# 9_-Power.net
KiCad netlist of a schematic drawn in Altium Designer
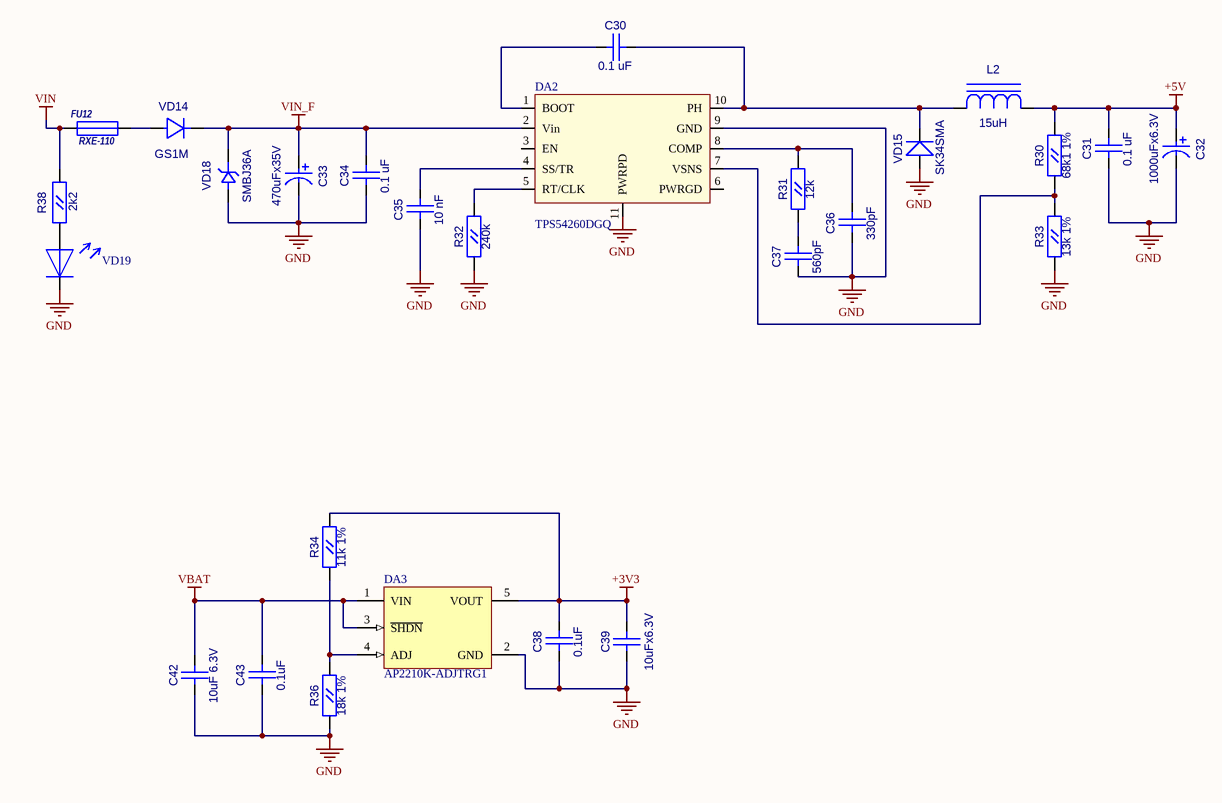
[diagram p0: [9]-Power.SchDoc]

(export (version "E")
  (design (tool "Eeschema 10.0.6"))
  (components
    (comp (ref "C30")
      (value "0.1 uF")
      (footprint "CC0603")
      (description "CC0603")
      (libsource (lib "gprs_modem_2") (part "CC0603"))
    )
    (comp (ref "C31")
      (value "0.1 uF")
      (footprint "CC0603")
      (description "CC0603")
      (libsource (lib "gprs_modem_2") (part "CC0603"))
    )
    (comp (ref "C32")
      (value "1000uFx6.3V")
      (footprint "CC8X3.5")
      (description "CAP0.35")
      (libsource (lib "gprs_modem_2") (part "CAP0.35"))
    )
    (comp (ref "C33")
      (value "470uFx35V")
      (footprint "CC16X10_CAP0.5(1)(Primary)")
      (description "CAP0.5(1)")
      (libsource (lib "gprs_modem_2") (part "CAP0.5(1)"))
    )
    (comp (ref "C34")
      (value "0.1 uF")
      (footprint "CC0603")
      (description "CC0603")
      (libsource (lib "gprs_modem_2") (part "CC0603"))
    )
    (comp (ref "C35")
      (value "10 nF")
      (footprint "CC0603")
      (description "CC0603")
      (libsource (lib "gprs_modem_2") (part "CC0603"))
    )
    (comp (ref "C36")
      (value "330pF")
      (footprint "CC0603")
      (description "CC0603")
      (libsource (lib "gprs_modem_2") (part "CC0603"))
    )
    (comp (ref "C37")
      (value "560pF")
      (footprint "CC0603")
      (description "CC0603")
      (libsource (lib "gprs_modem_2") (part "CC0603"))
    )
    (comp (ref "C38")
      (value "0.1uF")
      (footprint "CC0603")
      (description "CC0603")
      (libsource (lib "gprs_modem_2") (part "CC0603"))
    )
    (comp (ref "C39")
      (value "10uFx6.3V")
      (footprint "CC0805")
      (description "CC0805")
      (libsource (lib "gprs_modem_2") (part "CC0805"))
    )
    (comp (ref "C42")
      (value "10uF 6.3V")
      (footprint "CC0805")
      (description "CC0805")
      (libsource (lib "gprs_modem_2") (part "CC0805"))
    )
    (comp (ref "C43")
      (value "0.1uF")
      (footprint "CC0603")
      (description "CC0603")
      (libsource (lib "gprs_modem_2") (part "CC0603"))
    )
    (comp (ref "DA2")
      (value "TPS54260DGQ")
      (footprint "S-PDSO-G10")
      (libsource (lib "gprs_modem_2") (part "TPS54260DGQ"))
    )
    (comp (ref "DA3")
      (value "AP2210K-ADJTRG1")
      (footprint "SOT23-5")
      (fields (field (name "PUBLISHER") "Altium Limited"))
      (libsource (lib "gprs_modem_2") (part "MCP1824T-ADJE/OT"))
    )
    (comp (ref "FU12")
      (value "RXE-110")
      (footprint "RXE-110")
      (libsource (lib "gprs_modem_2") (part "RXE-110"))
    )
    (comp (ref "L2")
      (value "15uH")
      (footprint "SDR0805")
      (description "SDR0805")
      (libsource (lib "gprs_modem_2") (part "SDR0805"))
    )
    (comp (ref "R30")
      (value "68k1 1%")
      (footprint "RC0603")
      (description "RC0603")
      (libsource (lib "gprs_modem_2") (part "RC0603"))
    )
    (comp (ref "R31")
      (value "12k")
      (footprint "RC0603")
      (description "RC0603")
      (libsource (lib "gprs_modem_2") (part "RC0603"))
    )
    (comp (ref "R32")
      (value "240k")
      (footprint "RC0603")
      (description "RC0603")
      (libsource (lib "gprs_modem_2") (part "RC0603"))
    )
    (comp (ref "R33")
      (value "13k 1%")
      (footprint "RC0603")
      (description "RC0603")
      (libsource (lib "gprs_modem_2") (part "RC0603"))
    )
    (comp (ref "R34")
      (value "11k 1%")
      (footprint "RC0603")
      (description "RC0603")
      (libsource (lib "gprs_modem_2") (part "RC0603"))
    )
    (comp (ref "R36")
      (value "18k 1%")
      (footprint "RC0603")
      (description "RC0603")
      (libsource (lib "gprs_modem_2") (part "RC0603"))
    )
    (comp (ref "R38")
      (value "2k2")
      (footprint "RC0603")
      (description "RC0603")
      (libsource (lib "gprs_modem_2") (part "RC0603"))
    )
    (comp (ref "VD14") (value "GS1M") (footprint "SMA") (libsource (lib "gprs_modem_2") (part "GS1M")))
    (comp (ref "VD15")
      (value "SK34SMA")
      (footprint "SMA")
      (description "Schottky Rectifier")
      (libsource (lib "gprs_modem") (part "SK34SMA"))
    )
    (comp (ref "VD18") (value "SMBJ36A") (footprint "SMB") (libsource (lib "gprs_modem_2") (part "SMBJ")))
    (comp (ref "VD19")
      (value "LED_0805")
      (footprint "LED0805")
      (libsource (lib "gprs_modem_2") (part "LED_0805"))
    )
  )
  (nets
    (net (code "1") (name "+3V3") (class "Default")
      (node (ref "C38") (pin "1") (pinfunction "A_1") (pintype "passive"))
      (node (ref "C39") (pin "2") (pinfunction "B_2") (pintype "passive"))
      (node (ref "DA3") (pin "5") (pinfunction "VOUT_5") (pintype "power_in"))
      (node (ref "R34") (pin "2") (pinfunction "B_2") (pintype "passive"))
    )
    (net (code "2") (name "+5V") (class "Default")
      (node (ref "C31") (pin "1") (pinfunction "A_1") (pintype "passive"))
      (node (ref "C32") (pin "1") (pintype "passive"))
      (node (ref "L2") (pin "2") (pinfunction "A_2") (pintype "passive"))
      (node (ref "R30") (pin "2") (pinfunction "B_2") (pintype "passive"))
    )
    (net (code "3") (name "GND") (class "Default")
      (node (ref "C31") (pin "2") (pinfunction "B_2") (pintype "passive"))
      (node (ref "C32") (pin "2") (pintype "passive"))
      (node (ref "C33") (pin "1") (pintype "passive"))
      (node (ref "C34") (pin "2") (pinfunction "B_2") (pintype "passive"))
      (node (ref "C35") (pin "2") (pinfunction "B_2") (pintype "passive"))
      (node (ref "C36") (pin "2") (pinfunction "B_2") (pintype "passive"))
      (node (ref "C37") (pin "2") (pinfunction "B_2") (pintype "passive"))
      (node (ref "C38") (pin "2") (pinfunction "B_2") (pintype "passive"))
      (node (ref "C39") (pin "1") (pinfunction "A_1") (pintype "passive"))
      (node (ref "C42") (pin "1") (pinfunction "A_1") (pintype "passive"))
      (node (ref "C43") (pin "2") (pinfunction "B_2") (pintype "passive"))
      (node (ref "DA2") (pin "11") (pinfunction "PWRPD_11") (pintype "passive"))
      (node (ref "DA2") (pin "9") (pinfunction "GND_9") (pintype "passive"))
      (node (ref "DA3") (pin "2") (pinfunction "GND_2") (pintype "power_in"))
      (node (ref "R32") (pin "1") (pinfunction "A_1") (pintype "passive"))
      (node (ref "R33") (pin "1") (pinfunction "A_1") (pintype "passive"))
      (node (ref "R36") (pin "1") (pinfunction "A_1") (pintype "passive"))
      (node (ref "VD15") (pin "1") (pinfunction "A_1") (pintype "passive"))
      (node (ref "VD18") (pin "1") (pinfunction "A_1") (pintype "passive"))
      (node (ref "VD19") (pin "2") (pintype "passive"))
    )
    (net (code "4") (name "Net-(C30-A)") (class "Default")
      (node (ref "C30") (pin "1") (pinfunction "A_1") (pintype "passive"))
      (node (ref "DA2") (pin "10") (pinfunction "PH_10") (pintype "passive"))
      (node (ref "L2") (pin "1") (pinfunction "C_1") (pintype "passive"))
      (node (ref "VD15") (pin "2") (pinfunction "K_2") (pintype "passive"))
    )
    (net (code "5") (name "Net-(C30-B)") (class "Default")
      (node (ref "C30") (pin "2") (pinfunction "B_2") (pintype "passive"))
      (node (ref "DA2") (pin "1") (pinfunction "BOOT_1") (pintype "passive"))
    )
    (net (code "6") (name "Net-(C35-A)") (class "Default")
      (node (ref "C35") (pin "1") (pinfunction "A_1") (pintype "passive"))
      (node (ref "DA2") (pin "4") (pinfunction "SS/TR_4") (pintype "passive"))
    )
    (net (code "7") (name "Net-(C36-A)") (class "Default")
      (node (ref "C36") (pin "1") (pinfunction "A_1") (pintype "passive"))
      (node (ref "DA2") (pin "8") (pinfunction "COMP_8") (pintype "passive"))
      (node (ref "R31") (pin "2") (pinfunction "B_2") (pintype "passive"))
    )
    (net (code "8") (name "Net-(C37-A)") (class "Default")
      (node (ref "C37") (pin "1") (pinfunction "A_1") (pintype "passive"))
      (node (ref "R31") (pin "1") (pinfunction "A_1") (pintype "passive"))
    )
    (net (code "9") (name "Net-(DA2-RT{slash}CLK)") (class "Default")
      (node (ref "DA2") (pin "5") (pinfunction "RT/CLK_5") (pintype "passive"))
      (node (ref "R32") (pin "2") (pinfunction "B_2") (pintype "passive"))
    )
    (net (code "10") (name "Net-(DA2-VSNS)") (class "Default")
      (node (ref "DA2") (pin "7") (pinfunction "VSNS_7") (pintype "passive"))
      (node (ref "R30") (pin "1") (pinfunction "A_1") (pintype "passive"))
      (node (ref "R33") (pin "2") (pinfunction "B_2") (pintype "passive"))
    )
    (net (code "11") (name "Net-(DA3-ADJ)") (class "Default")
      (node (ref "DA3") (pin "4") (pinfunction "ADJ_4") (pintype "input"))
      (node (ref "R34") (pin "1") (pinfunction "A_1") (pintype "passive"))
      (node (ref "R36") (pin "2") (pinfunction "B_2") (pintype "passive"))
    )
    (net (code "12") (name "Net-(R38-A)") (class "Default")
      (node (ref "R38") (pin "1") (pinfunction "A_1") (pintype "passive"))
      (node (ref "VD19") (pin "1") (pintype "passive"))
    )
    (net (code "13") (name "Net-(VD14-A)") (class "Default")
      (node (ref "FU12") (pin "2") (pintype "passive"))
      (node (ref "VD14") (pin "1") (pinfunction "A_1") (pintype "passive"))
    )
    (net (code "14") (name "VBAT") (class "Default")
      (node (ref "C42") (pin "2") (pinfunction "B_2") (pintype "passive"))
      (node (ref "C43") (pin "1") (pinfunction "A_1") (pintype "passive"))
      (node (ref "DA3") (pin "1") (pinfunction "VIN_1") (pintype "power_in"))
      (node (ref "DA3") (pin "3") (pinfunction "~{SHDN}_3") (pintype "input"))
    )
    (net (code "15") (name "VIN") (class "Default")
      (node (ref "FU12") (pin "1") (pintype "passive"))
      (node (ref "R38") (pin "2") (pinfunction "B_2") (pintype "passive"))
    )
    (net (code "16") (name "VIN_F") (class "Default")
      (node (ref "C33") (pin "2") (pintype "passive"))
      (node (ref "C34") (pin "1") (pinfunction "A_1") (pintype "passive"))
      (node (ref "DA2") (pin "2") (pinfunction "Vin_2") (pintype "passive"))
      (node (ref "VD14") (pin "2") (pinfunction "K_2") (pintype "passive"))
      (node (ref "VD18") (pin "2") (pinfunction "K_2") (pintype "passive"))
    )
    (net (code "17") (name "unconnected-(DA2-EN-Pad3)") (class "Default")
      (node (ref "DA2") (pin "3") (pinfunction "EN_3") (pintype "passive"))
    )
    (net (code "18") (name "unconnected-(DA2-PWRGD-Pad6)") (class "Default")
      (node (ref "DA2") (pin "6") (pinfunction "PWRGD_6") (pintype "passive"))
    )
  )
)
